# OLED-GYRO.net
KiCad netlist of a schematic drawn in EAGLE
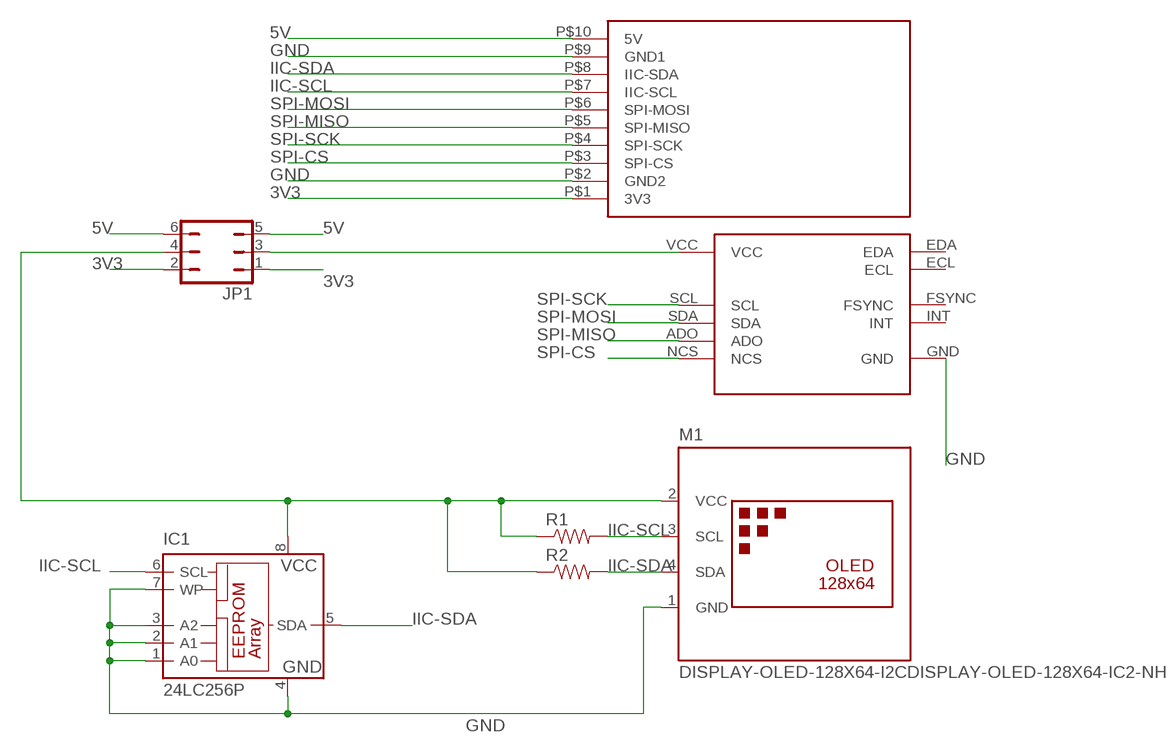
[diagram p0: schematic, sheet 1]

(export (version "E")
  (design (tool "Eeschema 10.0.6"))
  (components
    (comp (ref "IC1")
      (value "24LC256P")
      (footprint "eagle-import:DIL8")
      (fields (field (name "MF") "MICROCHIP") (field (name "MPN") "24LC256-E/P"))
      (libsource (lib "eagle-import") (part "24PLC256"))
    )
    (comp (ref "JP1")
      (value "JP3Q")
      (footprint "eagle-import:JP3Q")
      (libsource (lib "eagle-import") (part "JP3Q"))
    )
    (comp (ref "M1")
      (value "DISPLAY-OLED-128X64-I2CDISPLAY-OLED-128X64-IC2-NH")
      (footprint "eagle-import:DISPLAY-OLED-128X64-I2C_NH")
      (libsource (lib "eagle-import") (part "DISPLAY-OLED-128X64-I2CDISPLAY-OLED-128X64-IC2-NH"))
    )
    (comp (ref "R1")
      (value "RESISTORPTH-1/4W")
      (footprint "eagle-import:AXIAL-0.4")
      (libsource (lib "eagle-import") (part "RESISTORPTH-1/4W"))
    )
    (comp (ref "R2")
      (value "RESISTORPTH-1/4W")
      (footprint "eagle-import:AXIAL-0.4")
      (libsource (lib "eagle-import") (part "RESISTORPTH-1/4W"))
    )
    (comp (ref "U$1")
      (value "E4_SPI-IIC")
      (footprint "eagle-import:E4_SPI-IIC")
      (libsource (lib "eagle-import") (part "E4_SPI-IIC"))
    )
    (comp (ref "U$2")
      (value "MPU-9250/6500")
      (footprint "eagle-import:MPU9265")
      (libsource (lib "eagle-import") (part "MPU-9250/6500"))
    )
  )
  (nets
    (net (code "1") (name "/3V3") (class "Default")
      (node (ref "JP1") (pin "1") (pinfunction "1_1") (pintype "passive"))
      (node (ref "JP1") (pin "2") (pinfunction "2_2") (pintype "passive"))
      (node (ref "U$1") (pin "P$1") (pinfunction "3V3_P$1") (pintype "power_in"))
    )
    (net (code "2") (name "/5V") (class "Default")
      (node (ref "JP1") (pin "5") (pinfunction "5_5") (pintype "passive"))
      (node (ref "JP1") (pin "6") (pinfunction "6_6") (pintype "passive"))
      (node (ref "U$1") (pin "P$10") (pinfunction "5V_P$10") (pintype "power_in"))
    )
    (net (code "3") (name "/GND") (class "Default")
      (node (ref "IC1") (pin "1") (pinfunction "A0_1") (pintype "input"))
      (node (ref "IC1") (pin "2") (pinfunction "A1_2") (pintype "input"))
      (node (ref "IC1") (pin "3") (pinfunction "A2_3") (pintype "input"))
      (node (ref "IC1") (pin "4") (pinfunction "GND_4") (pintype "power_in"))
      (node (ref "IC1") (pin "7") (pinfunction "WP_7") (pintype "input"))
      (node (ref "M1") (pin "1") (pinfunction "GND_1") (pintype "power_in"))
      (node (ref "U$1") (pin "P$2") (pinfunction "GND2_P$2") (pintype "power_in"))
      (node (ref "U$1") (pin "P$9") (pinfunction "GND1_P$9") (pintype "power_in"))
      (node (ref "U$2") (pin "GND") (pinfunction "GND_GND") (pintype "bidirectional"))
    )
    (net (code "4") (name "/IIC-SCL") (class "Default")
      (node (ref "IC1") (pin "6") (pinfunction "SCL_6") (pintype "input"))
      (node (ref "M1") (pin "3") (pinfunction "SCL_3") (pintype "bidirectional"))
      (node (ref "R1") (pin "P$2") (pinfunction "2_P$2") (pintype "passive"))
      (node (ref "U$1") (pin "P$7") (pinfunction "IIC-SCL_P$7") (pintype "bidirectional"))
    )
    (net (code "5") (name "/IIC-SDA") (class "Default")
      (node (ref "IC1") (pin "5") (pinfunction "SDA_5") (pintype "bidirectional"))
      (node (ref "M1") (pin "4") (pinfunction "SDA_4") (pintype "bidirectional"))
      (node (ref "R2") (pin "P$2") (pinfunction "2_P$2") (pintype "passive"))
      (node (ref "U$1") (pin "P$8") (pinfunction "IIC-SDA_P$8") (pintype "bidirectional"))
    )
    (net (code "6") (name "/SPI-CS") (class "Default")
      (node (ref "U$1") (pin "P$3") (pinfunction "SPI-CS_P$3") (pintype "bidirectional"))
      (node (ref "U$2") (pin "NCS") (pinfunction "NCS_NCS") (pintype "bidirectional"))
    )
    (net (code "7") (name "/SPI-MISO") (class "Default")
      (node (ref "U$1") (pin "P$5") (pinfunction "SPI-MISO_P$5") (pintype "bidirectional"))
      (node (ref "U$2") (pin "ADO") (pinfunction "ADO_ADO") (pintype "bidirectional"))
    )
    (net (code "8") (name "/SPI-MOSI") (class "Default")
      (node (ref "U$1") (pin "P$6") (pinfunction "SPI-MOSI_P$6") (pintype "bidirectional"))
      (node (ref "U$2") (pin "SDA") (pinfunction "SDA_SDA") (pintype "bidirectional"))
    )
    (net (code "9") (name "/SPI-SCK") (class "Default")
      (node (ref "U$1") (pin "P$4") (pinfunction "SPI-SCK_P$4") (pintype "bidirectional"))
      (node (ref "U$2") (pin "SCL") (pinfunction "SCL_SCL") (pintype "bidirectional"))
    )
    (net (code "10") (name "Net-(IC1-VCC)") (class "Default")
      (node (ref "IC1") (pin "8") (pinfunction "VCC_8") (pintype "power_in"))
      (node (ref "JP1") (pin "4") (pinfunction "4_4") (pintype "passive"))
      (node (ref "M1") (pin "2") (pinfunction "VCC_2") (pintype "power_in"))
      (node (ref "R1") (pin "P$1") (pinfunction "1_P$1") (pintype "passive"))
      (node (ref "R2") (pin "P$1") (pinfunction "1_P$1") (pintype "passive"))
    )
    (net (code "11") (name "Net-(JP1-Pad3)") (class "Default")
      (node (ref "JP1") (pin "3") (pinfunction "3_3") (pintype "passive"))
      (node (ref "U$2") (pin "VCC") (pinfunction "VCC_VCC") (pintype "bidirectional"))
    )
    (net (code "12") (name "unconnected-(U$2-PadECL)") (class "Default")
      (node (ref "U$2") (pin "ECL") (pinfunction "ECL_ECL") (pintype "bidirectional"))
    )
    (net (code "13") (name "unconnected-(U$2-PadEDA)") (class "Default")
      (node (ref "U$2") (pin "EDA") (pinfunction "EDA_EDA") (pintype "bidirectional"))
    )
    (net (code "14") (name "unconnected-(U$2-PadFSYNC)") (class "Default")
      (node (ref "U$2") (pin "FSYNC") (pinfunction "FSYNC_FSYNC") (pintype "bidirectional"))
    )
    (net (code "15") (name "unconnected-(U$2-PadINT)") (class "Default")
      (node (ref "U$2") (pin "INT") (pinfunction "INT_INT") (pintype "bidirectional"))
    )
  )
)
